# RS232_Module_3V3.net
KiCad netlist of a schematic drawn in Altium Designer
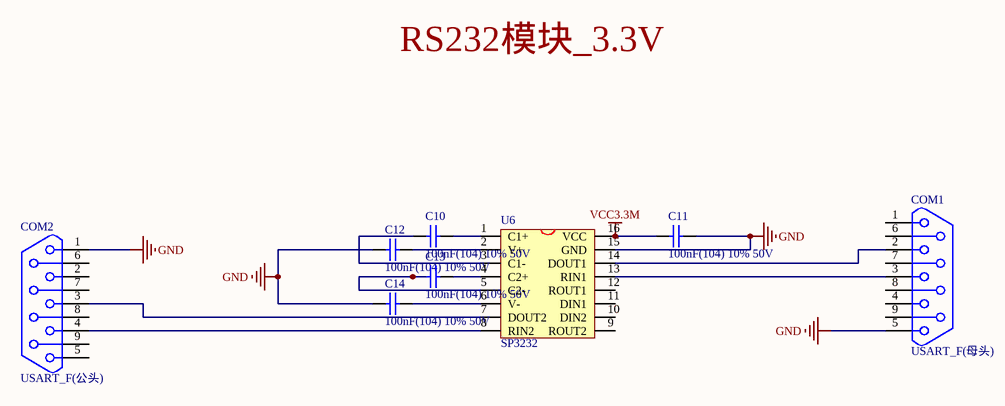
[diagram p0: RS232_Module_3V3.SchDoc]

(export (version "E")
  (design (tool "Eeschema 10.0.6"))
  (components
    (comp (ref "C10")
      (value "100nF(104) 10% 50V")
      (footprint "0805_C")
      (description "贴片电容")
      (libsource (lib "Miscellaneous Devices LC") (part "0805 100nF(104) 10% 50V"))
    )
    (comp (ref "C11")
      (value "100nF(104) 10% 50V")
      (footprint "0805_C")
      (description "贴片电容")
      (libsource (lib "Miscellaneous Devices LC") (part "0805 100nF(104) 10% 50V"))
    )
    (comp (ref "C12")
      (value "100nF(104) 10% 50V")
      (footprint "0805_C")
      (description "贴片电容")
      (libsource (lib "Miscellaneous Devices LC") (part "0805 100nF(104) 10% 50V"))
    )
    (comp (ref "C13")
      (value "100nF(104) 10% 50V")
      (footprint "0805_C")
      (description "贴片电容")
      (libsource (lib "Miscellaneous Devices LC") (part "0805 100nF(104) 10% 50V"))
    )
    (comp (ref "C14")
      (value "100nF(104) 10% 50V")
      (footprint "0805_C")
      (description "贴片电容")
      (libsource (lib "Miscellaneous Devices LC") (part "0805 100nF(104) 10% 50V"))
    )
    (comp (ref "COM1") (value "USART_F(母头)") (footprint "DB9") (libsource (lib "") (part "DB9_1")))
    (comp (ref "COM2")
      (value "USART_F(公头)")
      (footprint "DB9")
      (libsource (lib "Explorer STM32F407封装库") (part "DB9"))
    )
    (comp (ref "U6")
      (value "SP3232")
      (footprint "SOP16M")
      (libsource (lib "Explorer STM32F407封装库") (part "MAX3232"))
    )
  )
  (nets
    (net (code "1") (name "GND") (class "Default")
      (node (ref "C11") (pin "2") (pinfunction "2_2") (pintype "passive"))
      (node (ref "C12") (pin "1") (pinfunction "1_1") (pintype "passive"))
      (node (ref "C14") (pin "1") (pinfunction "1_1") (pintype "passive"))
      (node (ref "COM1") (pin "5") (pinfunction "5_5") (pintype "passive"))
      (node (ref "COM2") (pin "1") (pinfunction "1_1") (pintype "passive"))
      (node (ref "U6") (pin "15") (pinfunction "GND_15") (pintype "passive"))
    )
    (net (code "2") (name "Net-(U6-C1+)") (class "Default")
      (node (ref "C10") (pin "2") (pinfunction "2_2") (pintype "passive"))
      (node (ref "U6") (pin "1") (pinfunction "C1+_1") (pintype "passive"))
    )
    (net (code "3") (name "Net-(U6-C1-)") (class "Default")
      (node (ref "C10") (pin "1") (pinfunction "1_1") (pintype "passive"))
      (node (ref "U6") (pin "3") (pinfunction "C1-_3") (pintype "passive"))
    )
    (net (code "4") (name "Net-(U6-C2+)") (class "Default")
      (node (ref "C13") (pin "2") (pinfunction "2_2") (pintype "passive"))
      (node (ref "U6") (pin "4") (pinfunction "C2+_4") (pintype "passive"))
    )
    (net (code "5") (name "Net-(U6-C2-)") (class "Default")
      (node (ref "C13") (pin "1") (pinfunction "1_1") (pintype "passive"))
      (node (ref "U6") (pin "5") (pinfunction "C2-_5") (pintype "passive"))
    )
    (net (code "6") (name "Net-(U6-DOUT1)") (class "Default")
      (node (ref "COM1") (pin "2") (pinfunction "2_2") (pintype "passive"))
      (node (ref "U6") (pin "14") (pinfunction "DOUT1_14") (pintype "passive"))
    )
    (net (code "7") (name "Net-(U6-DOUT2)") (class "Default")
      (node (ref "COM2") (pin "3") (pinfunction "3_3") (pintype "passive"))
      (node (ref "U6") (pin "7") (pinfunction "DOUT2_7") (pintype "passive"))
    )
    (net (code "8") (name "Net-(U6-RIN1)") (class "Default")
      (node (ref "COM1") (pin "3") (pinfunction "3_3") (pintype "passive"))
      (node (ref "U6") (pin "13") (pinfunction "RIN1_13") (pintype "passive"))
    )
    (net (code "9") (name "Net-(U6-RIN2)") (class "Default")
      (node (ref "COM2") (pin "4") (pinfunction "4_4") (pintype "passive"))
      (node (ref "U6") (pin "8") (pinfunction "RIN2_8") (pintype "passive"))
    )
    (net (code "10") (name "Net-(U6-V+)") (class "Default")
      (node (ref "C12") (pin "2") (pinfunction "2_2") (pintype "passive"))
      (node (ref "U6") (pin "2") (pinfunction "V+_2") (pintype "passive"))
    )
    (net (code "11") (name "Net-(U6-V-)") (class "Default")
      (node (ref "C14") (pin "2") (pinfunction "2_2") (pintype "passive"))
      (node (ref "U6") (pin "6") (pinfunction "V-_6") (pintype "passive"))
    )
    (net (code "12") (name "VCC3.3M") (class "Default")
      (node (ref "C11") (pin "1") (pinfunction "1_1") (pintype "passive"))
      (node (ref "U6") (pin "16") (pinfunction "VCC_16") (pintype "passive"))
    )
    (net (code "13") (name "unconnected-(COM1-Pad1)") (class "Default")
      (node (ref "COM1") (pin "1") (pinfunction "1_1") (pintype "passive"))
    )
    (net (code "14") (name "unconnected-(COM1-Pad4)") (class "Default")
      (node (ref "COM1") (pin "4") (pinfunction "4_4") (pintype "passive"))
    )
    (net (code "15") (name "unconnected-(COM1-Pad6)") (class "Default")
      (node (ref "COM1") (pin "6") (pinfunction "6_6") (pintype "passive"))
    )
    (net (code "16") (name "unconnected-(COM1-Pad7)") (class "Default")
      (node (ref "COM1") (pin "7") (pinfunction "7_7") (pintype "passive"))
    )
    (net (code "17") (name "unconnected-(COM1-Pad8)") (class "Default")
      (node (ref "COM1") (pin "8") (pinfunction "8_8") (pintype "passive"))
    )
    (net (code "18") (name "unconnected-(COM1-Pad9)") (class "Default")
      (node (ref "COM1") (pin "9") (pinfunction "9_9") (pintype "passive"))
    )
    (net (code "19") (name "unconnected-(COM2-Pad2)") (class "Default")
      (node (ref "COM2") (pin "2") (pinfunction "2_2") (pintype "passive"))
    )
    (net (code "20") (name "unconnected-(COM2-Pad5)") (class "Default")
      (node (ref "COM2") (pin "5") (pinfunction "5_5") (pintype "passive"))
    )
    (net (code "21") (name "unconnected-(COM2-Pad6)") (class "Default")
      (node (ref "COM2") (pin "6") (pinfunction "6_6") (pintype "passive"))
    )
    (net (code "22") (name "unconnected-(COM2-Pad7)") (class "Default")
      (node (ref "COM2") (pin "7") (pinfunction "7_7") (pintype "passive"))
    )
    (net (code "23") (name "unconnected-(COM2-Pad8)") (class "Default")
      (node (ref "COM2") (pin "8") (pinfunction "8_8") (pintype "passive"))
    )
    (net (code "24") (name "unconnected-(COM2-Pad9)") (class "Default")
      (node (ref "COM2") (pin "9") (pinfunction "9_9") (pintype "passive"))
    )
    (net (code "25") (name "unconnected-(U6-DIN1-Pad11)") (class "Default")
      (node (ref "U6") (pin "11") (pinfunction "DIN1_11") (pintype "passive"))
    )
    (net (code "26") (name "unconnected-(U6-DIN2-Pad10)") (class "Default")
      (node (ref "U6") (pin "10") (pinfunction "DIN2_10") (pintype "passive"))
    )
    (net (code "27") (name "unconnected-(U6-ROUT1-Pad12)") (class "Default")
      (node (ref "U6") (pin "12") (pinfunction "ROUT1_12") (pintype "passive"))
    )
    (net (code "28") (name "unconnected-(U6-ROUT2-Pad9)") (class "Default")
      (node (ref "U6") (pin "9") (pinfunction "ROUT2_9") (pintype "passive"))
    )
  )
)
